# TS12A4514DBVR.net
KiCad netlist of a schematic drawn in Altium Designer
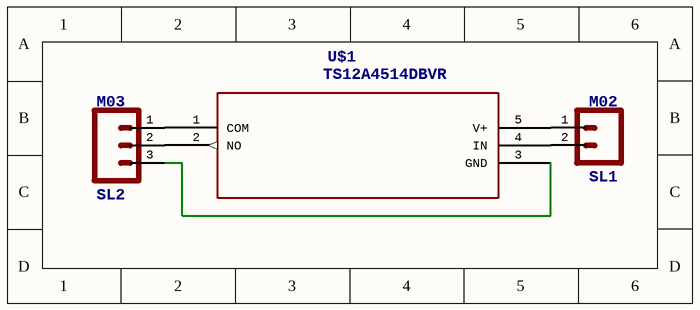
[diagram p0: TS12A4514DBVR.SchDoc]

(export (version "E")
  (design (tool "Eeschema 10.0.6"))
  (components
    (comp (ref "SL1")
      (value "M02")
      (footprint "02P")
      (description "<b>AMP QUICK CONNECTOR</b>")
      (libsource (lib "con-amp-quick") (part "M02"))
    )
    (comp (ref "SL2")
      (value "M03")
      (footprint "03P")
      (description "<b>AMP QUICK CONNECTOR</b>")
      (libsource (lib "con-amp-quick") (part "M03"))
    )
    (comp (ref "U$1")
      (value "TS12A4514DBVR")
      (footprint "DBV5")
      (fields
        (field (name "GENERIC_PART_NUMBER") "TS12A4514")
        (field (name "MANUFACTURER") "Texas Instruments")
        (field (name "COPYRIGHT") "Copyright C 2015 Accelerated Designs. All rights reserved")
      )
      (libsource (lib "TS12A4514DBVR") (part "TS12A4514DBVR"))
    )
  )
  (nets
    (net (code "1") (name "Net-(U$1-COM)") (class "Default")
      (node (ref "SL2") (pin "1") (pinfunction "1_1") (pintype "passive"))
      (node (ref "U$1") (pin "1") (pinfunction "COM_1") (pintype "passive"))
    )
    (net (code "2") (name "Net-(U$1-GND)") (class "Default")
      (node (ref "SL2") (pin "3") (pinfunction "3_3") (pintype "passive"))
      (node (ref "U$1") (pin "3") (pinfunction "GND_3") (pintype "power_in"))
    )
    (net (code "3") (name "Net-(U$1-IN)") (class "Default")
      (node (ref "SL1") (pin "2") (pinfunction "2_2") (pintype "passive"))
      (node (ref "U$1") (pin "4") (pinfunction "IN_4") (pintype "passive"))
    )
    (net (code "4") (name "Net-(U$1-NO)") (class "Default")
      (node (ref "SL2") (pin "2") (pinfunction "2_2") (pintype "passive"))
      (node (ref "U$1") (pin "2") (pinfunction "NO_2") (pintype "output"))
    )
    (net (code "5") (name "Net-(U$1-V+)") (class "Default")
      (node (ref "SL1") (pin "1") (pinfunction "1_1") (pintype "passive"))
      (node (ref "U$1") (pin "5") (pinfunction "V+_5") (pintype "power_in"))
    )
  )
)
